# 3_amplifier.net
KiCad netlist of a schematic drawn in Altium Designer
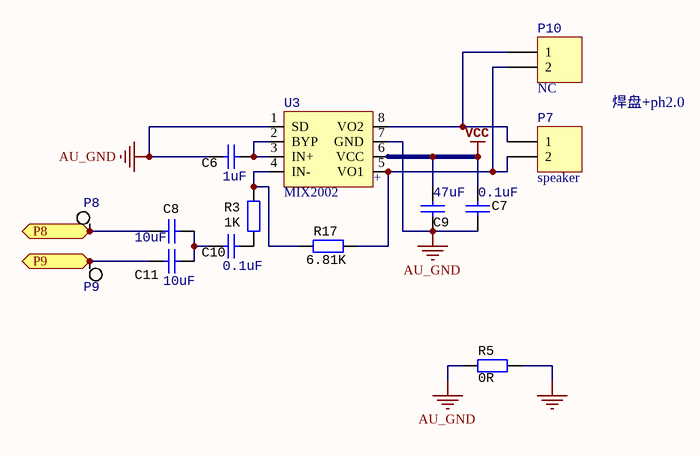
[diagram p0: 3 amplifier.SchDoc]

(export (version "E")
  (design (tool "Eeschema 10.0.6"))
  (components
    (comp (ref "C6")
      (value "1uF")
      (footprint "0402")
      (description "CAP, CERM, 0.01uF, 100V, +/-5%, X7R, 0603")
      (fields (field (name "PARTNUMBER") "06031C103JAT2A") (field (name "MANUFACTURER") "AVX"))
      (libsource (lib "03.常用器件") (part "CAP1_npol"))
    )
    (comp (ref "C7")
      (value "0.1uF")
      (footprint "0402")
      (description "CAP, CERM, 0.01uF, 100V, +/-5%, X7R, 0603")
      (fields (field (name "PARTNUMBER") "06031C103JAT2A") (field (name "MANUFACTURER") "AVX"))
      (libsource (lib "03.常用器件") (part "CAP1_npol"))
    )
    (comp (ref "C8")
      (value "10uF")
      (footprint "0603")
      (description "CAP, CERM, 0.01uF, 100V, +/-5%, X7R, 0603")
      (fields (field (name "PARTNUMBER") "06031C103JAT2A") (field (name "MANUFACTURER") "AVX"))
      (libsource (lib "03.常用器件") (part "CAP1_npol"))
    )
    (comp (ref "C9")
      (value "47uF")
      (footprint "0805")
      (description "CAP, CERM, 0.01uF, 100V, +/-5%, X7R, 0603")
      (fields (field (name "PARTNUMBER") "06031C103JAT2A") (field (name "MANUFACTURER") "AVX"))
      (libsource (lib "03.常用器件") (part "CAP1_npol"))
    )
    (comp (ref "C10")
      (value "0.1uF")
      (footprint "0402")
      (description "CAP, CERM, 0.01uF, 100V, +/-5%, X7R, 0603")
      (fields (field (name "PARTNUMBER") "06031C103JAT2A") (field (name "MANUFACTURER") "AVX"))
      (libsource (lib "03.常用器件") (part "CAP1_npol"))
    )
    (comp (ref "C11")
      (value "10uF")
      (footprint "0603")
      (description "CAP, CERM, 0.01uF, 100V, +/-5%, X7R, 0603")
      (fields (field (name "PARTNUMBER") "06031C103JAT2A") (field (name "MANUFACTURER") "AVX"))
      (libsource (lib "03.常用器件") (part "CAP1_npol"))
    )
    (comp (ref "P7")
      (value "speaker")
      (footprint "焊盘")
      (description "Header, 2-Pin")
      (fields (field (name "PUBLISHER") "Altium Limited"))
      (libsource (lib "Miscellaneous Connectors") (part "Header 2"))
    )
    (comp (ref "P8")
      (value "~")
      (footprint "测试点")
      (description "Test Point")
      (libsource (lib "my_Schlib") (part "TP"))
    )
    (comp (ref "P9")
      (value "~")
      (footprint "测试点")
      (description "Test Point")
      (libsource (lib "my_Schlib") (part "TP"))
    )
    (comp (ref "P10")
      (value "NC")
      (footprint "2PIN/2.0MM座子")
      (description "Header, 2-Pin")
      (fields (field (name "PUBLISHER") "Altium Limited"))
      (libsource (lib "Miscellaneous Connectors") (part "Header 2"))
    )
    (comp (ref "R3")
      (value "1K")
      (footprint "0402")
      (description "RES, 1.0k ohm, 5%, 0.1W, 0603")
      (fields
        (field (name "PARTNUMBER") "RC0603JR-071KL")
        (field (name "MANUFACTURER") "Yageo America")
        (field (name "PUBLISHER") "Texas Instruments")
      )
      (libsource (lib "") (part "RES1_1"))
    )
    (comp (ref "R5")
      (value "0R")
      (footprint "0402")
      (description "RES, 1.0k ohm, 5%, 0.1W, 0603")
      (fields
        (field (name "PARTNUMBER") "RC0603JR-071KL")
        (field (name "MANUFACTURER") "Yageo America")
        (field (name "PUBLISHER") "Texas Instruments")
      )
      (libsource (lib "03.常用器件") (part "RES1"))
    )
    (comp (ref "R17")
      (value "6.81K")
      (footprint "0402")
      (description "RES, 1.0k ohm, 5%, 0.1W, 0603")
      (fields
        (field (name "PARTNUMBER") "RC0603JR-071KL")
        (field (name "MANUFACTURER") "Yageo America")
        (field (name "PUBLISHER") "Texas Instruments")
      )
      (libsource (lib "") (part "RES1_2"))
    )
    (comp (ref "U3") (value "MIX2002") (footprint "SOP-8") (libsource (lib "Schlib1") (part "MIX2002")))
  )
  (nets
    (net (code "1") (name "/P8") (class "Default")
      (node (ref "C8") (pin "2") (pinfunction "2_2") (pintype "passive"))
      (node (ref "P8") (pin "1") (pinfunction "1_1") (pintype "passive"))
    )
    (net (code "2") (name "/P9") (class "Default")
      (node (ref "C11") (pin "2") (pinfunction "2_2") (pintype "passive"))
      (node (ref "P9") (pin "1") (pinfunction "1_1") (pintype "passive"))
    )
    (net (code "3") (name "<NO NET>") (class "Default")
      (node (ref "R5") (pin "1") (pinfunction "1_1") (pintype "passive"))
    )
    (net (code "4") (name "AU_GND") (class "Default")
      (node (ref "C6") (pin "1") (pinfunction "1_1") (pintype "passive"))
      (node (ref "C7") (pin "2") (pinfunction "2_2") (pintype "passive"))
      (node (ref "C9") (pin "2") (pinfunction "2_2") (pintype "passive"))
      (node (ref "R5") (pin "2") (pinfunction "2_2") (pintype "passive"))
      (node (ref "U3") (pin "1") (pinfunction "SD_1") (pintype "passive"))
      (node (ref "U3") (pin "7") (pinfunction "GND_7") (pintype "passive"))
    )
    (net (code "5") (name "Net-(C10-Pad1)") (class "Default")
      (node (ref "C10") (pin "1") (pinfunction "1_1") (pintype "passive"))
      (node (ref "C11") (pin "1") (pinfunction "1_1") (pintype "passive"))
      (node (ref "C8") (pin "1") (pinfunction "1_1") (pintype "passive"))
    )
    (net (code "6") (name "Net-(C10-Pad2)") (class "Default")
      (node (ref "C10") (pin "2") (pinfunction "2_2") (pintype "passive"))
      (node (ref "R3") (pin "1") (pinfunction "1_1") (pintype "passive"))
    )
    (net (code "7") (name "Net-(U3-BYP)") (class "Default")
      (node (ref "C6") (pin "2") (pinfunction "2_2") (pintype "passive"))
      (node (ref "U3") (pin "2") (pinfunction "BYP_2") (pintype "passive"))
      (node (ref "U3") (pin "3") (pinfunction "IN+_3") (pintype "passive"))
    )
    (net (code "8") (name "Net-(U3-IN-)") (class "Default")
      (node (ref "R17") (pin "1") (pinfunction "1_1") (pintype "passive"))
      (node (ref "R3") (pin "2") (pinfunction "2_2") (pintype "passive"))
      (node (ref "U3") (pin "4") (pinfunction "IN-_4") (pintype "passive"))
    )
    (net (code "9") (name "Net-(U3-VO1)") (class "Default")
      (node (ref "P10") (pin "2") (pinfunction "2_2") (pintype "passive"))
      (node (ref "P7") (pin "2") (pinfunction "2_2") (pintype "passive"))
      (node (ref "R17") (pin "2") (pinfunction "2_2") (pintype "passive"))
      (node (ref "U3") (pin "5") (pinfunction "VO1_5") (pintype "passive"))
    )
    (net (code "10") (name "Net-(U3-VO2)") (class "Default")
      (node (ref "P10") (pin "1") (pinfunction "1_1") (pintype "passive"))
      (node (ref "P7") (pin "1") (pinfunction "1_1") (pintype "passive"))
      (node (ref "U3") (pin "8") (pinfunction "VO2_8") (pintype "passive"))
    )
    (net (code "11") (name "VCC") (class "Default")
      (node (ref "C7") (pin "1") (pinfunction "1_1") (pintype "passive"))
      (node (ref "C9") (pin "1") (pinfunction "1_1") (pintype "passive"))
      (node (ref "U3") (pin "6") (pinfunction "VCC_6") (pintype "passive"))
    )
  )
)
